# Power.net
KiCad netlist of a schematic drawn in Altium Designer
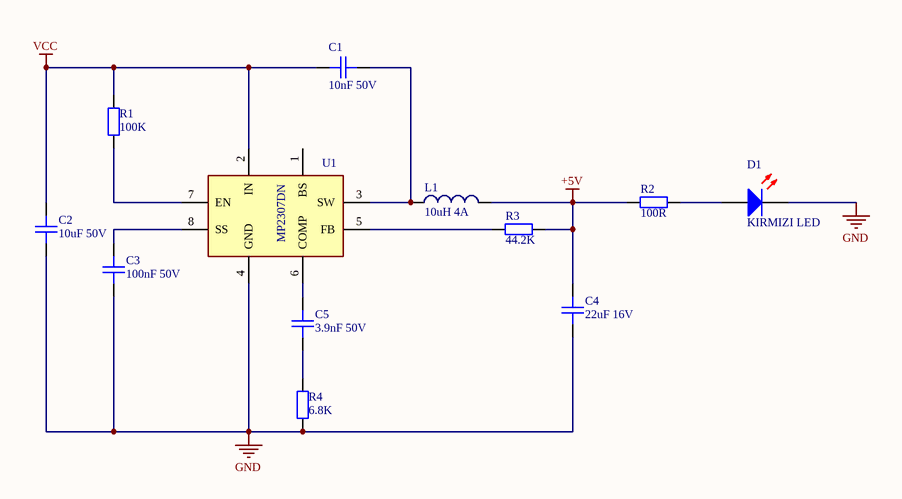
[diagram p0: Power.SchDoc]

(export (version "E")
  (design (tool "Eeschema 10.0.6"))
  (components
    (comp (ref "C1")
      (value "CAP CER 10000PF 50V X7R 0805")
      (footprint "CAP 0805/2012")
      (description "10000pF ±10% 50V Ceramic Capacitor X7R 0805 (2012 Metric)")
      (fields (field (name "DEGER") "10nF 50V"))
      (libsource (lib "PROJE") (part "10nF 50V 0805"))
    )
    (comp (ref "C2")
      (value "CAP CER 10UF 50V X5R 1206")
      (footprint "CAP 1206/3216")
      (description "10µF ±10% 50V Ceramic Capacitor X5R 1206 (3216 Metric)")
      (fields (field (name "DEGER") "10uF 50V"))
      (libsource (lib "PROJE") (part "10uF 50V 1206"))
    )
    (comp (ref "C3")
      (value "CAP CER 0.1UF 50V X7R 0805")
      (footprint "CAP 0805/2012")
      (description "0.1µF ±10% 50V Ceramic Capacitor X7R 0805 (2012 Metric)")
      (fields (field (name "DEGER") "100nF 50V"))
      (libsource (lib "PROJE") (part "100nF 50V 0805"))
    )
    (comp (ref "C4")
      (value "CAP CERAMIC 22UF 16V X7S 20% PAD")
      (footprint "CAP 1206/3216")
      (description "22µF ±20% 16V Ceramic Capacitor X7S 1206 (3216 Metric)")
      (fields (field (name "DEGER") "22uF 16V"))
      (libsource (lib "PROJE") (part "22uF 16V 1206"))
    )
    (comp (ref "C5")
      (value "CAP CER 3900PF 50V X7R 0805")
      (footprint "CAP 0805/2012")
      (description "3900pF ±10% 50V Ceramic Capacitor X7R 0805 (2012 Metric)")
      (fields (field (name "DEGER") "3.9nF 50V"))
      (libsource (lib "PROJE") (part "3.9nF 50V 0805"))
    )
    (comp (ref "D1")
      (value "Red 645nm LED Indication - Discrete 1.8V 0805")
      (footprint "SMD: LED 0805/2012 RED")
      (description "LED RED DIFFUSED 0805 SMD")
      (fields (field (name "DEGER") "KIRMIZI LED"))
      (libsource (lib "PROJE") (part "LED_Kırmızı"))
    )
    (comp (ref "L1")
      (value "FIXED IND 10UH 4A 68 MOHM SMD")
      (footprint "ASPI-0630LR-100M-T15")
      (description "10µH Shielded Molded Inductor 4A 68mOhm Max Nonstandard")
      (fields (field (name "DEGER") "10uH 4A"))
      (libsource (lib "PROJE") (part "10uH 4A"))
    )
    (comp (ref "R1")
      (value "RES SMD 100K OHM 1% 1/8W 0805")
      (footprint "RES_0805")
      (description "100 kOhms ±1% 0.125W, 1/8W Chip Resistor 0805 (2012 Metric) Moisture Resistant Thick Film")
      (fields (field (name "DEGER") "100K"))
      (libsource (lib "PROJE") (part "100K 0805"))
    )
    (comp (ref "R2")
      (value "RES SMD 100 OHM 1% 1/8W 0805")
      (footprint "RES_0805")
      (description "100 Ohms ±1% 0.125W, 1/8W Chip Resistor 0805 (2012 Metric) Moisture Resistant Thick Film")
      (fields (field (name "DEGER") "100R"))
      (libsource (lib "PROJE") (part "100R 0805"))
    )
    (comp (ref "R3")
      (value "RES SMD 44.2K OHM 1% 1/8W 0805")
      (footprint "RES_0805")
      (description "44.2 kOhms ±1% 0.125W, 1/8W Chip Resistor 0805 (2012 Metric) Moisture Resistant Thick Film")
      (fields (field (name "DEGER") "44.2K"))
      (libsource (lib "PROJE") (part "44.2K 0805"))
    )
    (comp (ref "R4")
      (value "RES SMD 6.8K OHM 1% 1/8W 0805")
      (footprint "RES_0805")
      (description "6.8 kOhms ±1% 0.125W, 1/8W Chip Resistor 0805 (2012 Metric) Moisture Resistant Thick Film")
      (fields (field (name "DEGER") "6.8K"))
      (libsource (lib "PROJE") (part "6.8K 0805"))
    )
    (comp (ref "U1")
      (value "IC REG BUCK ADJUSTABLE 3A 8SOIC")
      (footprint "SOIC8_PAD")
      (fields (field (name "DEGER") "MP2307DN"))
      (libsource (lib "PROJE") (part "MP2307DN"))
    )
  )
  (nets
    (net (code "1") (name "+5V") (class "Default")
      (node (ref "C4") (pin "2") (pinfunction "2_2") (pintype "passive"))
      (node (ref "L1") (pin "2") (pinfunction "2_2") (pintype "passive"))
      (node (ref "R2") (pin "1") (pinfunction "1_1") (pintype "passive"))
      (node (ref "R3") (pin "2") (pinfunction "2_2") (pintype "passive"))
    )
    (net (code "2") (name "GND") (class "Default")
      (node (ref "C2") (pin "1") (pinfunction "1_1") (pintype "passive"))
      (node (ref "C3") (pin "1") (pinfunction "1_1") (pintype "passive"))
      (node (ref "C4") (pin "1") (pinfunction "1_1") (pintype "passive"))
      (node (ref "D1") (pin "2") (pinfunction "K_2") (pintype "passive"))
      (node (ref "R4") (pin "1") (pinfunction "1_1") (pintype "passive"))
      (node (ref "U1") (pin "4") (pinfunction "GND_4") (pintype "passive"))
    )
    (net (code "3") (name "Net-(C5-Pad1)") (class "Default")
      (node (ref "C5") (pin "1") (pinfunction "1_1") (pintype "passive"))
      (node (ref "R4") (pin "2") (pinfunction "2_2") (pintype "passive"))
    )
    (net (code "4") (name "Net-(D1-A)") (class "Default")
      (node (ref "D1") (pin "1") (pinfunction "A_1") (pintype "passive"))
      (node (ref "R2") (pin "2") (pinfunction "2_2") (pintype "passive"))
    )
    (net (code "5") (name "Net-(U1-COMP)") (class "Default")
      (node (ref "C5") (pin "2") (pinfunction "2_2") (pintype "passive"))
      (node (ref "U1") (pin "6") (pinfunction "COMP_6") (pintype "passive"))
    )
    (net (code "6") (name "Net-(U1-EN)") (class "Default")
      (node (ref "R1") (pin "1") (pinfunction "1_1") (pintype "passive"))
      (node (ref "U1") (pin "7") (pinfunction "EN_7") (pintype "passive"))
    )
    (net (code "7") (name "Net-(U1-FB)") (class "Default")
      (node (ref "R3") (pin "1") (pinfunction "1_1") (pintype "passive"))
      (node (ref "U1") (pin "5") (pinfunction "FB_5") (pintype "passive"))
    )
    (net (code "8") (name "Net-(U1-SS)") (class "Default")
      (node (ref "C3") (pin "2") (pinfunction "2_2") (pintype "passive"))
      (node (ref "U1") (pin "8") (pinfunction "SS_8") (pintype "passive"))
    )
    (net (code "9") (name "Net-(U1-SW)") (class "Default")
      (node (ref "C1") (pin "1") (pinfunction "1_1") (pintype "passive"))
      (node (ref "L1") (pin "1") (pinfunction "1_1") (pintype "passive"))
      (node (ref "U1") (pin "3") (pinfunction "SW_3") (pintype "passive"))
    )
    (net (code "10") (name "VCC") (class "Default")
      (node (ref "C1") (pin "2") (pinfunction "2_2") (pintype "passive"))
      (node (ref "C2") (pin "2") (pinfunction "2_2") (pintype "passive"))
      (node (ref "R1") (pin "2") (pinfunction "2_2") (pintype "passive"))
      (node (ref "U1") (pin "2") (pinfunction "IN_2") (pintype "passive"))
    )
    (net (code "11") (name "unconnected-(U1-BS-Pad1)") (class "Default")
      (node (ref "U1") (pin "1") (pinfunction "BS_1") (pintype "passive"))
    )
  )
)
